# ReceptorTori.net
KiCad netlist of a schematic drawn in EAGLE
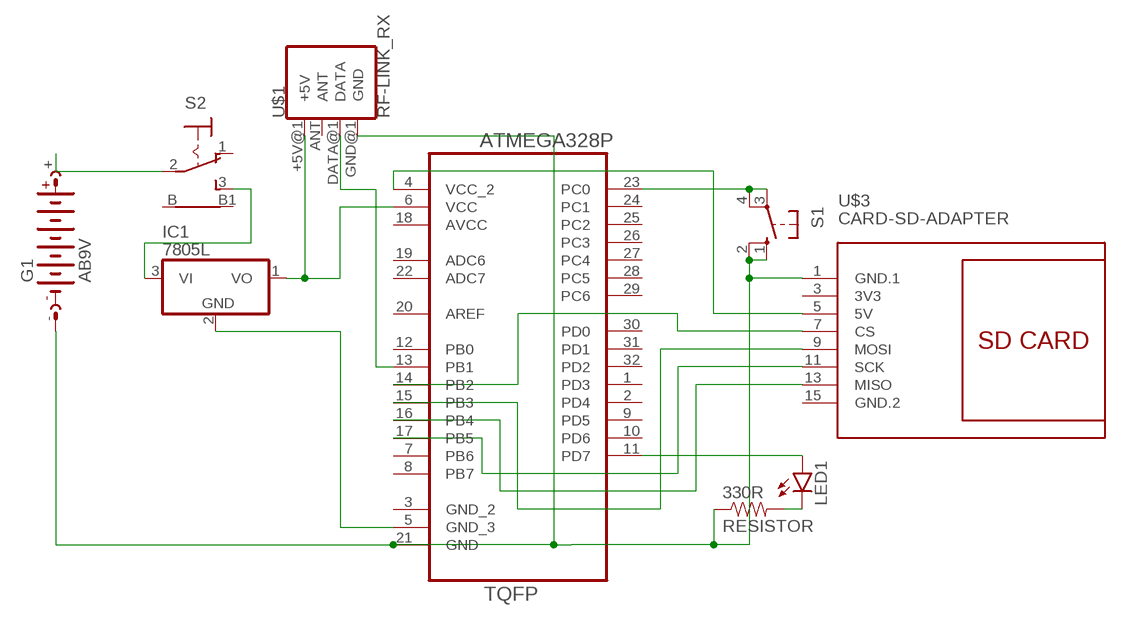
[diagram p0: schematic, sheet 1]

(export (version "E")
  (design (tool "Eeschema 10.0.6"))
  (components
    (comp (ref "330R")
      (value "RESISTOR")
      (footprint "eagle-import:0603RES")
      (libsource (lib "eagle-import") (part "RESISTOR"))
    )
    (comp (ref "G1")
      (value "AB9V")
      (footprint "eagle-import:AB9V")
      (libsource (lib "eagle-import") (part "AB9V"))
    )
    (comp (ref "IC1")
      (value "7805L")
      (footprint "eagle-import:TO92")
      (libsource (lib "eagle-import") (part "78L05"))
    )
    (comp (ref "LED1")
      (value "LED5MM")
      (footprint "eagle-import:LED5MM")
      (libsource (lib "eagle-import") (part "LED5MM"))
    )
    (comp (ref "S1")
      (value "10-XX")
      (footprint "eagle-import:B3F-10XX")
      (fields (field (name "MPN") "B3F-1000"))
      (libsource (lib "eagle-import") (part "10-XX"))
    )
    (comp (ref "S2")
      (value "9070-1W")
      (footprint "eagle-import:9070-1W")
      (libsource (lib "eagle-import") (part "9070-1W"))
    )
    (comp (ref "U$1")
      (value "RF-LINK_RX")
      (footprint "eagle-import:RF-LINK_RX")
      (libsource (lib "eagle-import") (part "RF-LINK_RX"))
    )
    (comp (ref "U$3")
      (value "CARD-SD-ADAPTER")
      (footprint "eagle-import:CARD-SD-ADAPTER")
      (libsource (lib "eagle-import") (part "CARD-SD-ADAPTER"))
    )
    (comp (ref "U1")
      (value "ATMEGA328P-AU")
      (footprint "eagle-import:QFP80P900X900X120-32N")
      (libsource (lib "eagle-import") (part "ATMEGA328P-AU"))
    )
  )
  (nets
    (net (code "1") (name "/3V3") (class "Default")
      (node (ref "U$3") (pin "3") (pinfunction "3V3_3") (pintype "power_in"))
    )
    (net (code "2") (name "/AVCC") (class "Default")
      (node (ref "U1") (pin "18") (pinfunction "AVCC_18") (pintype "power_in"))
    )
    (net (code "3") (name "/GND.2") (class "Default")
      (node (ref "U$3") (pin "15") (pinfunction "GND.2_15") (pintype "power_in"))
    )
    (net (code "4") (name "Net-(IC1-GND)") (class "Default")
      (node (ref "IC1") (pin "2") (pinfunction "GND_2") (pintype "passive"))
      (node (ref "U1") (pin "5") (pinfunction "GND_3_5") (pintype "passive"))
    )
    (net (code "5") (name "Net-(IC1-VI)") (class "Default")
      (node (ref "IC1") (pin "3") (pinfunction "VI_3") (pintype "input"))
      (node (ref "S2") (pin "3") (pinfunction "S_3") (pintype "passive"))
    )
    (net (code "6") (name "Net-(IC1-VO)") (class "Default")
      (node (ref "IC1") (pin "1") (pinfunction "VO_1") (pintype "passive"))
      (node (ref "U$1") (pin "+5V@1") (pinfunction "+5V_+5V@1") (pintype "power_in"))
      (node (ref "U1") (pin "6") (pinfunction "VCC_6") (pintype "power_in"))
    )
    (net (code "7") (name "Net-(LED1-C)") (class "Default")
      (node (ref "330R") (pin "2") (pinfunction "2_2") (pintype "passive"))
      (node (ref "LED1") (pin "K") (pinfunction "C_K") (pintype "passive"))
    )
    (net (code "8") (name "Net-(S1-P)") (class "Default")
      (node (ref "S1") (pin "3") (pinfunction "P_3") (pintype "passive"))
      (node (ref "S1") (pin "4") (pinfunction "P1_4") (pintype "passive"))
      (node (ref "U1") (pin "23") (pinfunction "PC0_23") (pintype "bidirectional"))
    )
    (net (code "9") (name "Net-(S1-S)") (class "Default")
      (node (ref "330R") (pin "1") (pinfunction "1_1") (pintype "passive"))
      (node (ref "G1") (pin "-") (pinfunction "-_-") (pintype "passive"))
      (node (ref "S1") (pin "1") (pinfunction "S_1") (pintype "passive"))
      (node (ref "S1") (pin "2") (pinfunction "S1_2") (pintype "passive"))
      (node (ref "U$1") (pin "GND@1") (pinfunction "GND_GND@1") (pintype "power_in"))
      (node (ref "U$3") (pin "1") (pinfunction "GND.1_1") (pintype "power_in"))
      (node (ref "U1") (pin "21") (pinfunction "GND_21") (pintype "passive"))
    )
    (net (code "10") (name "Net-(S2-P)") (class "Default")
      (node (ref "G1") (pin "+") (pinfunction "+_+") (pintype "passive"))
      (node (ref "S2") (pin "2") (pinfunction "P_2") (pintype "passive"))
    )
    (net (code "11") (name "Net-(U$1-DATA)") (class "Default")
      (node (ref "U$1") (pin "DATA@1") (pinfunction "DATA_DATA@1") (pintype "input"))
      (node (ref "U1") (pin "13") (pinfunction "PB1_13") (pintype "bidirectional"))
    )
    (net (code "12") (name "Net-(U$3-5V)") (class "Default")
      (node (ref "U$3") (pin "5") (pinfunction "5V_5") (pintype "power_in"))
      (node (ref "U1") (pin "4") (pinfunction "VCC_2_4") (pintype "power_in"))
    )
    (net (code "13") (name "Net-(U$3-CS)") (class "Default")
      (node (ref "U$3") (pin "7") (pinfunction "CS_7") (pintype "bidirectional"))
      (node (ref "U1") (pin "14") (pinfunction "PB2_14") (pintype "bidirectional"))
    )
    (net (code "14") (name "Net-(U$3-MISO)") (class "Default")
      (node (ref "U$3") (pin "13") (pinfunction "MISO_13") (pintype "bidirectional"))
      (node (ref "U1") (pin "16") (pinfunction "PB4_16") (pintype "bidirectional"))
    )
    (net (code "15") (name "Net-(U$3-MOSI)") (class "Default")
      (node (ref "U$3") (pin "9") (pinfunction "MOSI_9") (pintype "bidirectional"))
      (node (ref "U1") (pin "15") (pinfunction "PB3_15") (pintype "bidirectional"))
    )
    (net (code "16") (name "Net-(U$3-SCK)") (class "Default")
      (node (ref "U$3") (pin "11") (pinfunction "SCK_11") (pintype "bidirectional"))
      (node (ref "U1") (pin "17") (pinfunction "PB5_17") (pintype "bidirectional"))
    )
    (net (code "17") (name "Net-(U1-PD7)") (class "Default")
      (node (ref "LED1") (pin "A") (pinfunction "A_A") (pintype "passive"))
      (node (ref "U1") (pin "11") (pinfunction "PD7_11") (pintype "bidirectional"))
    )
    (net (code "18") (name "unconnected-(S2-O-Pad1)") (class "Default")
      (node (ref "S2") (pin "1") (pinfunction "O_1") (pintype "passive"))
    )
    (net (code "19") (name "unconnected-(S2-PadB)") (class "Default")
      (node (ref "S2") (pin "B") (pinfunction "B_B") (pintype "passive"))
    )
    (net (code "20") (name "unconnected-(S2-PadB1)") (class "Default")
      (node (ref "S2") (pin "B1") (pinfunction "B1_B1") (pintype "passive"))
    )
    (net (code "21") (name "unconnected-(U$1-PadANT)") (class "Default")
      (node (ref "U$1") (pin "ANT") (pinfunction "ANT_ANT") (pintype "passive"))
    )
    (net (code "22") (name "unconnected-(U1-ADC6-Pad19)") (class "Default")
      (node (ref "U1") (pin "19") (pinfunction "ADC6_19") (pintype "input"))
    )
    (net (code "23") (name "unconnected-(U1-ADC7-Pad22)") (class "Default")
      (node (ref "U1") (pin "22") (pinfunction "ADC7_22") (pintype "input"))
    )
    (net (code "24") (name "unconnected-(U1-AREF-Pad20)") (class "Default")
      (node (ref "U1") (pin "20") (pinfunction "AREF_20") (pintype "input"))
    )
    (net (code "25") (name "unconnected-(U1-GND_2-Pad3)") (class "Default")
      (node (ref "U1") (pin "3") (pinfunction "GND_2_3") (pintype "passive"))
    )
    (net (code "26") (name "unconnected-(U1-PB0-Pad12)") (class "Default")
      (node (ref "U1") (pin "12") (pinfunction "PB0_12") (pintype "bidirectional"))
    )
    (net (code "27") (name "unconnected-(U1-PB6-Pad7)") (class "Default")
      (node (ref "U1") (pin "7") (pinfunction "PB6_7") (pintype "bidirectional"))
    )
    (net (code "28") (name "unconnected-(U1-PB7-Pad8)") (class "Default")
      (node (ref "U1") (pin "8") (pinfunction "PB7_8") (pintype "bidirectional"))
    )
    (net (code "29") (name "unconnected-(U1-PC1-Pad24)") (class "Default")
      (node (ref "U1") (pin "24") (pinfunction "PC1_24") (pintype "bidirectional"))
    )
    (net (code "30") (name "unconnected-(U1-PC2-Pad25)") (class "Default")
      (node (ref "U1") (pin "25") (pinfunction "PC2_25") (pintype "bidirectional"))
    )
    (net (code "31") (name "unconnected-(U1-PC3-Pad26)") (class "Default")
      (node (ref "U1") (pin "26") (pinfunction "PC3_26") (pintype "bidirectional"))
    )
    (net (code "32") (name "unconnected-(U1-PC4-Pad27)") (class "Default")
      (node (ref "U1") (pin "27") (pinfunction "PC4_27") (pintype "bidirectional"))
    )
    (net (code "33") (name "unconnected-(U1-PC5-Pad28)") (class "Default")
      (node (ref "U1") (pin "28") (pinfunction "PC5_28") (pintype "bidirectional"))
    )
    (net (code "34") (name "unconnected-(U1-PC6-Pad29)") (class "Default")
      (node (ref "U1") (pin "29") (pinfunction "PC6_29") (pintype "bidirectional"))
    )
    (net (code "35") (name "unconnected-(U1-PD0-Pad30)") (class "Default")
      (node (ref "U1") (pin "30") (pinfunction "PD0_30") (pintype "bidirectional"))
    )
    (net (code "36") (name "unconnected-(U1-PD1-Pad31)") (class "Default")
      (node (ref "U1") (pin "31") (pinfunction "PD1_31") (pintype "bidirectional"))
    )
    (net (code "37") (name "unconnected-(U1-PD2-Pad32)") (class "Default")
      (node (ref "U1") (pin "32") (pinfunction "PD2_32") (pintype "bidirectional"))
    )
    (net (code "38") (name "unconnected-(U1-PD3-Pad1)") (class "Default")
      (node (ref "U1") (pin "1") (pinfunction "PD3_1") (pintype "bidirectional"))
    )
    (net (code "39") (name "unconnected-(U1-PD4-Pad2)") (class "Default")
      (node (ref "U1") (pin "2") (pinfunction "PD4_2") (pintype "bidirectional"))
    )
    (net (code "40") (name "unconnected-(U1-PD5-Pad9)") (class "Default")
      (node (ref "U1") (pin "9") (pinfunction "PD5_9") (pintype "bidirectional"))
    )
    (net (code "41") (name "unconnected-(U1-PD6-Pad10)") (class "Default")
      (node (ref "U1") (pin "10") (pinfunction "PD6_10") (pintype "bidirectional"))
    )
  )
)
